# CODEC_and_Headphone_Jack.net
KiCad netlist of a schematic drawn in Altium Designer
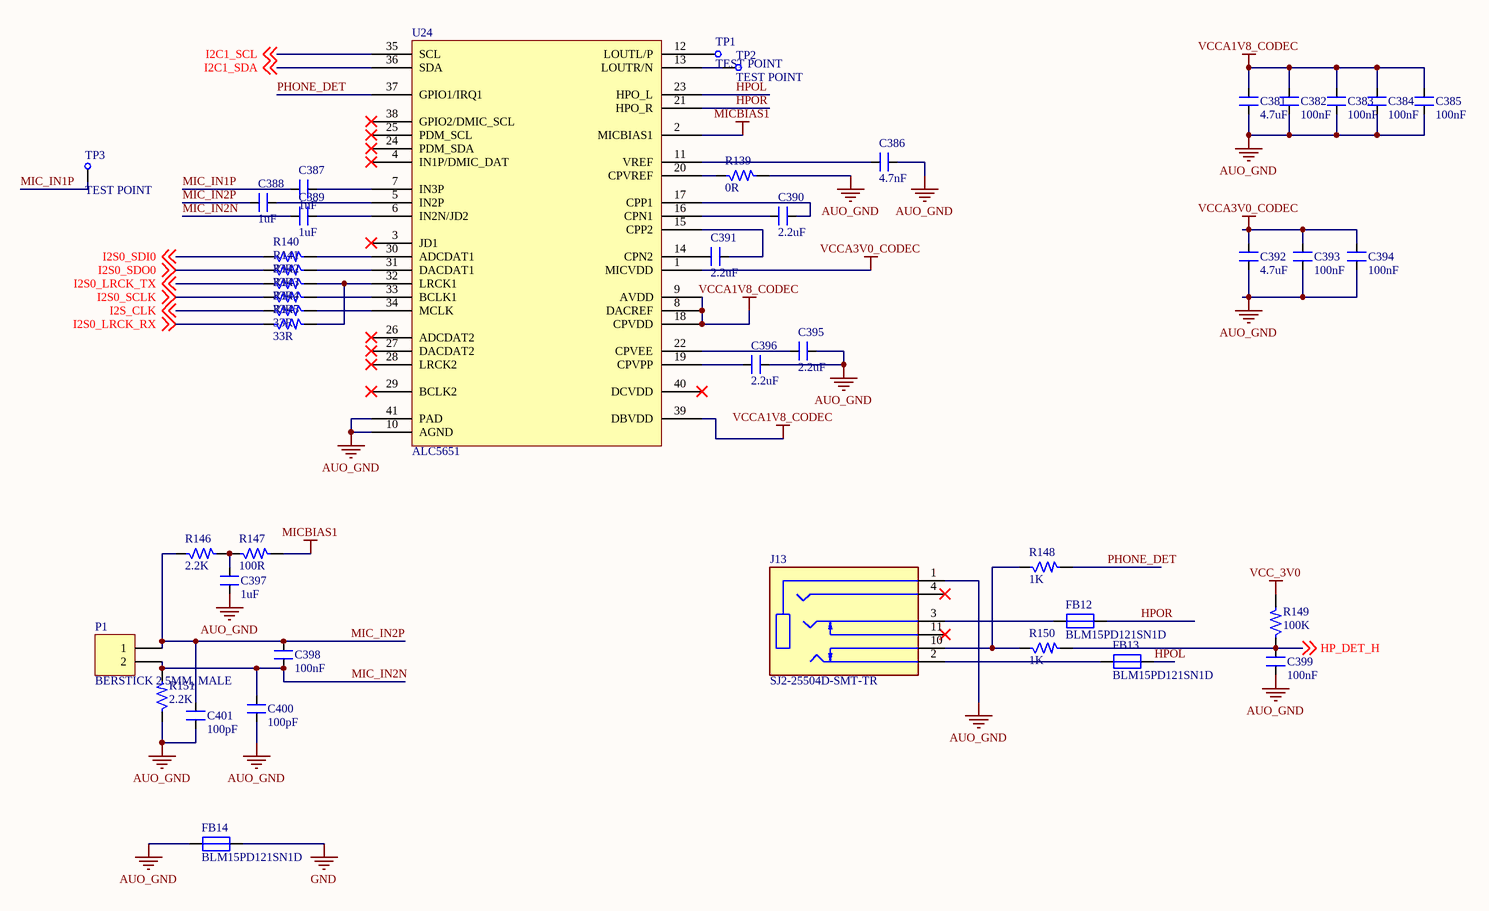
[diagram p0: CODEC and Headphone Jack.SchDoc]

(export (version "E")
  (design (tool "Eeschema 10.0.6"))
  (components
    (comp (ref "C381")
      (value "4.7uF")
      (footprint "CAP_0603")
      (description "4.7µF ±10% 16V Ceramic Capacitor X5R 0603 (1608 Metric)")
      (fields
        (field (name "MANUFACTURER") "Murata Electronics")
        (field (name "MANUFACTURER PART NUMBER") "GRM188R61C475KAAJD")
      )
      (libsource (lib "RK3399 _Module_Schlib") (part "CAP_4.7uF-16V-10%-0603"))
    )
    (comp (ref "C382")
      (value "100nF")
      (footprint "CAP_0603")
      (description "0.1µF ±10% 10V Ceramic Capacitor X7R 0603 (1608 Metric)")
      (fields
        (field (name "MANUFACTURER") "Yageo")
        (field (name "MANUFACTURER PART NUMBER") "CC0603KRX7R6BB104")
      )
      (libsource (lib "RK3399 _Module_Schlib") (part "CAP_100nF-10V-5%-0603"))
    )
    (comp (ref "C383")
      (value "100nF")
      (footprint "CAP_0603")
      (description "0.1µF ±10% 10V Ceramic Capacitor X7R 0603 (1608 Metric)")
      (fields
        (field (name "MANUFACTURER") "Yageo")
        (field (name "MANUFACTURER PART NUMBER") "CC0603KRX7R6BB104")
      )
      (libsource (lib "RK3399 _Module_Schlib") (part "CAP_100nF-10V-5%-0603"))
    )
    (comp (ref "C384")
      (value "100nF")
      (footprint "CAP_0603")
      (description "0.1µF ±10% 10V Ceramic Capacitor X7R 0603 (1608 Metric)")
      (fields
        (field (name "MANUFACTURER") "Yageo")
        (field (name "MANUFACTURER PART NUMBER") "CC0603KRX7R6BB104")
      )
      (libsource (lib "RK3399 _Module_Schlib") (part "CAP_100nF-10V-5%-0603"))
    )
    (comp (ref "C385")
      (value "100nF")
      (footprint "CAP_0603")
      (description "0.1µF ±10% 10V Ceramic Capacitor X7R 0603 (1608 Metric)")
      (fields
        (field (name "MANUFACTURER") "Yageo")
        (field (name "MANUFACTURER PART NUMBER") "CC0603KRX7R6BB104")
      )
      (libsource (lib "RK3399 _Module_Schlib") (part "CAP_100nF-10V-5%-0603"))
    )
    (comp (ref "C386")
      (value "4.7nF")
      (footprint "CAP_0603")
      (description "4700pF ±10% 10V Ceramic Capacitor X7R 0603 (1608 Metric)")
      (fields
        (field (name "MANUFACTURER") "KEMET")
        (field (name "MANUFACTURER PART NUMBER") "C0603C472K8RACTU")
      )
      (libsource (lib "RK3399 _Module_Schlib") (part "CAP_4.7nF-10V-10%-0603"))
    )
    (comp (ref "C387")
      (value "1uF")
      (footprint "CAP_0402")
      (description "1µF ±10% 10V Ceramic Capacitor X6S 0402 (1005 Metric)")
      (fields
        (field (name "MANUFACTURER") "Murata Electronics")
        (field (name "MANUFACTURER PART NUMBER") "GRT155C81A105KE01D")
      )
      (libsource (lib "RK3399 _Module_Schlib") (part "CAP_1uF-10V-10%-0402"))
    )
    (comp (ref "C388")
      (value "1uF")
      (footprint "CAP_0402")
      (description "1µF ±10% 10V Ceramic Capacitor X6S 0402 (1005 Metric)")
      (fields
        (field (name "MANUFACTURER") "Murata Electronics")
        (field (name "MANUFACTURER PART NUMBER") "GRT155C81A105KE01D")
      )
      (libsource (lib "RK3399 _Module_Schlib") (part "CAP_1uF-10V-10%-0402"))
    )
    (comp (ref "C389")
      (value "1uF")
      (footprint "CAP_0402")
      (description "1µF ±10% 10V Ceramic Capacitor X6S 0402 (1005 Metric)")
      (fields
        (field (name "MANUFACTURER") "Murata Electronics")
        (field (name "MANUFACTURER PART NUMBER") "GRT155C81A105KE01D")
      )
      (libsource (lib "RK3399 _Module_Schlib") (part "CAP_1uF-10V-10%-0402"))
    )
    (comp (ref "C390")
      (value "2.2uF")
      (footprint "CAP_0402")
      (description "2.2µF ±10% 10V Ceramic Capacitor X5R 0402 (1005 Metric)")
      (fields
        (field (name "MANUFACTURER") "Murata Electronics")
        (field (name "MANUFACTURER PART NUMBER") "GRM155R61A225KE95D")
      )
      (libsource (lib "RK3399 _Module_Schlib") (part "CAP_2.2uF-10V-10%-0402"))
    )
    (comp (ref "C391")
      (value "2.2uF")
      (footprint "CAP_0402")
      (description "2.2µF ±10% 10V Ceramic Capacitor X5R 0402 (1005 Metric)")
      (fields
        (field (name "MANUFACTURER") "Murata Electronics")
        (field (name "MANUFACTURER PART NUMBER") "GRM155R61A225KE95D")
      )
      (libsource (lib "RK3399 _Module_Schlib") (part "CAP_2.2uF-10V-10%-0402"))
    )
    (comp (ref "C392")
      (value "4.7uF")
      (footprint "CAP_0603")
      (description "4.7µF ±10% 16V Ceramic Capacitor X5R 0603 (1608 Metric)")
      (fields
        (field (name "MANUFACTURER") "Murata Electronics")
        (field (name "MANUFACTURER PART NUMBER") "GRM188R61C475KAAJD")
      )
      (libsource (lib "RK3399 _Module_Schlib") (part "CAP_4.7uF-16V-10%-0603"))
    )
    (comp (ref "C393")
      (value "100nF")
      (footprint "CAP_0603")
      (description "0.1µF ±10% 10V Ceramic Capacitor X7R 0603 (1608 Metric)")
      (fields
        (field (name "MANUFACTURER") "Yageo")
        (field (name "MANUFACTURER PART NUMBER") "CC0603KRX7R6BB104")
      )
      (libsource (lib "RK3399 _Module_Schlib") (part "CAP_100nF-10V-5%-0603"))
    )
    (comp (ref "C394")
      (value "100nF")
      (footprint "CAP_0603")
      (description "0.1µF ±10% 10V Ceramic Capacitor X7R 0603 (1608 Metric)")
      (fields
        (field (name "MANUFACTURER") "Yageo")
        (field (name "MANUFACTURER PART NUMBER") "CC0603KRX7R6BB104")
      )
      (libsource (lib "RK3399 _Module_Schlib") (part "CAP_100nF-10V-5%-0603"))
    )
    (comp (ref "C395")
      (value "2.2uF")
      (footprint "CAP_0402")
      (description "2.2µF ±10% 10V Ceramic Capacitor X5R 0402 (1005 Metric)")
      (fields
        (field (name "MANUFACTURER") "Murata Electronics")
        (field (name "MANUFACTURER PART NUMBER") "GRM155R61A225KE95D")
      )
      (libsource (lib "RK3399 _Module_Schlib") (part "CAP_2.2uF-10V-10%-0402"))
    )
    (comp (ref "C396")
      (value "2.2uF")
      (footprint "CAP_0402")
      (description "2.2µF ±10% 10V Ceramic Capacitor X5R 0402 (1005 Metric)")
      (fields
        (field (name "MANUFACTURER") "Murata Electronics")
        (field (name "MANUFACTURER PART NUMBER") "GRM155R61A225KE95D")
      )
      (libsource (lib "RK3399 _Module_Schlib") (part "CAP_2.2uF-10V-10%-0402"))
    )
    (comp (ref "C397")
      (value "1uF")
      (footprint "CAP_0603")
      (description "1µF ±10% 10V Ceramic Capacitor X5R 0603 (1608 Metric)")
      (fields
        (field (name "MANUFACTURER") "Samsung Electro-Mechanics")
        (field (name "MANUFACTURER PART NUMBER") "CL10A105KP8NNNC")
      )
      (libsource (lib "RK3399 _Module_Schlib") (part "CAP_1uF-10V-5%-0603"))
    )
    (comp (ref "C398")
      (value "100nF")
      (footprint "CAP_0603")
      (description "0.1µF ±10% 10V Ceramic Capacitor X7R 0603 (1608 Metric)")
      (fields
        (field (name "MANUFACTURER") "Yageo")
        (field (name "MANUFACTURER PART NUMBER") "CC0603KRX7R6BB104")
      )
      (libsource (lib "RK3399 _Module_Schlib") (part "CAP_100nF-10V-5%-0603"))
    )
    (comp (ref "C399")
      (value "100nF")
      (footprint "CAP_0603")
      (description "0.1µF ±10% 10V Ceramic Capacitor X7R 0603 (1608 Metric)")
      (fields
        (field (name "MANUFACTURER") "Yageo")
        (field (name "MANUFACTURER PART NUMBER") "CC0603KRX7R6BB104")
      )
      (libsource (lib "RK3399 _Module_Schlib") (part "CAP_100nF-10V-5%-0603"))
    )
    (comp (ref "C400")
      (value "100pF")
      (footprint "CAP_0603")
      (description "100pF ±10% 10V Ceramic Capacitor X7R 0603 (1608 Metric)")
      (fields
        (field (name "MANUFACTURER") "AVX Corporation")
        (field (name "MANUFACTURER PART NUMBER") "0603ZC101KAT2A")
      )
      (libsource (lib "RK3399 _Module_Schlib") (part "CAP_100pF-10V-10%-0603"))
    )
    (comp (ref "C401")
      (value "100pF")
      (footprint "CAP_0603")
      (description "100pF ±10% 10V Ceramic Capacitor X7R 0603 (1608 Metric)")
      (fields
        (field (name "MANUFACTURER") "AVX Corporation")
        (field (name "MANUFACTURER PART NUMBER") "0603ZC101KAT2A")
      )
      (libsource (lib "RK3399 _Module_Schlib") (part "CAP_100pF-10V-10%-0603"))
    )
    (comp (ref "FB12")
      (value "BLM15PD121SN1D")
      (footprint "RES_0402")
      (description "120 Ohms @ 100MHz 1 Power Line Ferrite Bead 0402 (1005 Metric) 1.3A 90mOhm")
      (fields (field (name "MANUFACTURER") "Murata Electronics"))
      (libsource (lib "RK3399 _Module_Schlib") (part "FB_120R-1.3A-100Mhz-0402"))
    )
    (comp (ref "FB13")
      (value "BLM15PD121SN1D")
      (footprint "RES_0402")
      (description "120 Ohms @ 100MHz 1 Power Line Ferrite Bead 0402 (1005 Metric) 1.3A 90mOhm")
      (fields (field (name "MANUFACTURER") "Murata Electronics"))
      (libsource (lib "RK3399 _Module_Schlib") (part "FB_120R-1.3A-100Mhz-0402"))
    )
    (comp (ref "FB14")
      (value "BLM15PD121SN1D")
      (footprint "RES_0402")
      (description "120 Ohms @ 100MHz 1 Power Line Ferrite Bead 0402 (1005 Metric) 1.3A 90mOhm")
      (fields (field (name "MANUFACTURER") "Murata Electronics"))
      (libsource (lib "RK3399 _Module_Schlib") (part "FB_120R-1.3A-100Mhz-0402"))
    )
    (comp (ref "J13")
      (value "SJ2-25504D-SMT-TR")
      (footprint "CON11_SJ2-25504D-SMT-TR_TH_RA")
      (fields (field (name "MANUFACTURER") "CUI Devices"))
      (libsource (lib "RK3399 _Module_Schlib") (part "CON-PLG_SJ2-25504D-SMT-TR-RA-TH"))
    )
    (comp (ref "P1")
      (value "BERSTICK 2.5MM, MALE")
      (footprint "CON2_100_43D62_TH_ST")
      (description "2 Pins, 1 Row 2.54mm Pitch, Straight bergstrip, Male")
      (fields (field (name "MANUFACTURER PART NUMBER") "NA") (field (name "MANUFACTURER") "Samtec"))
      (libsource (lib "RK3399 _Module_Schlib") (part "CON-BS-PLG_2X1-100-ST-TH"))
    )
    (comp (ref "R139")
      (value "0R")
      (footprint "RES_0603")
      (description "0 Ohms Jumper 0.1W, 1/10W Chip Resistor 0603 (1608 Metric) Thick Film")
      (fields
        (field (name "MANUFACTURER") "Yageo")
        (field (name "MANUFACTURER PART NUMBER") "RC0603JR-070RL")
      )
      (libsource (lib "RK3399 _Module_Schlib") (part "RES_0R-0.1W-1%-0603"))
    )
    (comp (ref "R140")
      (value "33R")
      (footprint "RES_0402")
      (description "33 Ohms ±1% 0.1W, 1/10W Chip Resistor 0402 (1005 Metric) Automotive AEC-Q200 Thick Film")
      (fields
        (field (name "MANUFACTURER") "Panasonic Electronic Components")
        (field (name "MANUFACTURER PART NUMBER") "ERJ-2RKF33R0X")
      )
      (libsource (lib "RK3399 _Module_Schlib") (part "RES_33R-0.1W-1%-0402"))
    )
    (comp (ref "R141")
      (value "33R")
      (footprint "RES_0402")
      (description "33 Ohms ±1% 0.1W, 1/10W Chip Resistor 0402 (1005 Metric) Automotive AEC-Q200 Thick Film")
      (fields
        (field (name "MANUFACTURER") "Panasonic Electronic Components")
        (field (name "MANUFACTURER PART NUMBER") "ERJ-2RKF33R0X")
      )
      (libsource (lib "RK3399 _Module_Schlib") (part "RES_33R-0.1W-1%-0402"))
    )
    (comp (ref "R142")
      (value "33R")
      (footprint "RES_0402")
      (description "33 Ohms ±1% 0.1W, 1/10W Chip Resistor 0402 (1005 Metric) Automotive AEC-Q200 Thick Film")
      (fields
        (field (name "MANUFACTURER") "Panasonic Electronic Components")
        (field (name "MANUFACTURER PART NUMBER") "ERJ-2RKF33R0X")
      )
      (libsource (lib "RK3399 _Module_Schlib") (part "RES_33R-0.1W-1%-0402"))
    )
    (comp (ref "R143")
      (value "33R")
      (footprint "RES_0402")
      (description "33 Ohms ±1% 0.1W, 1/10W Chip Resistor 0402 (1005 Metric) Automotive AEC-Q200 Thick Film")
      (fields
        (field (name "MANUFACTURER") "Panasonic Electronic Components")
        (field (name "MANUFACTURER PART NUMBER") "ERJ-2RKF33R0X")
      )
      (libsource (lib "RK3399 _Module_Schlib") (part "RES_33R-0.1W-1%-0402"))
    )
    (comp (ref "R144")
      (value "33R")
      (footprint "RES_0402")
      (description "33 Ohms ±1% 0.1W, 1/10W Chip Resistor 0402 (1005 Metric) Automotive AEC-Q200 Thick Film")
      (fields
        (field (name "MANUFACTURER") "Panasonic Electronic Components")
        (field (name "MANUFACTURER PART NUMBER") "ERJ-2RKF33R0X")
      )
      (libsource (lib "RK3399 _Module_Schlib") (part "RES_33R-0.1W-1%-0402"))
    )
    (comp (ref "R145")
      (value "33R")
      (footprint "RES_0402")
      (description "33 Ohms ±1% 0.1W, 1/10W Chip Resistor 0402 (1005 Metric) Automotive AEC-Q200 Thick Film")
      (fields
        (field (name "MANUFACTURER") "Panasonic Electronic Components")
        (field (name "MANUFACTURER PART NUMBER") "ERJ-2RKF33R0X")
      )
      (libsource (lib "RK3399 _Module_Schlib") (part "RES_33R-0.1W-1%-0402"))
    )
    (comp (ref "R146")
      (value "2.2K")
      (footprint "RES_0603")
      (description "2.2 kOhms ±1% 0.1W, 1/10W Chip Resistor 0603 (1608 Metric) Thick Film")
      (fields
        (field (name "MANUFACTURER") "Yageo")
        (field (name "MANUFACTURER PART NUMBER") "RC0603FR-072K2L")
      )
      (libsource (lib "RK3399 _Module_Schlib") (part "RES_2.2K-0.1W-1%-0603"))
    )
    (comp (ref "R147")
      (value "100R")
      (footprint "RES_0603")
      (description "100 Ohms ±1% 0.1W, 1/10W Chip Resistor 0603 (1608 Metric) Thick Film")
      (fields
        (field (name "MANUFACTURER") "Yageo")
        (field (name "MANUFACTURER PART NUMBER") "RC0603FR-07100RL")
      )
      (libsource (lib "RK3399 _Module_Schlib") (part "RES_100R-0.1W-1%-0603"))
    )
    (comp (ref "R148")
      (value "1K")
      (footprint "RES_0603")
      (description "1 kOhms ±1% 0.1W, 1/10W Chip Resistor 0603 (1608 Metric) Thick Film")
      (fields
        (field (name "MANUFACTURER") "Yageo")
        (field (name "MANUFACTURER PART NUMBER") "RC0603FR-071KL")
      )
      (libsource (lib "RK3399 _Module_Schlib") (part "RES_1K-0.1W-1%-0603"))
    )
    (comp (ref "R149")
      (value "100K")
      (footprint "RES_0603")
      (description "100 kOhms ±1% 0.1W, 1/10W Chip Resistor 0603 (1608 Metric) Automotive AEC-Q200 Thick Film")
      (fields
        (field (name "MANUFACTURER") "tackpole Electronics Inc")
        (field (name "MANUFACTURER PART NUMBER") "RMCF0603FT100K")
      )
      (libsource (lib "RK3399 _Module_Schlib") (part "RES_100K-0.1W-1%-0603"))
    )
    (comp (ref "R150")
      (value "1K")
      (footprint "RES_0603")
      (description "1 kOhms ±1% 0.1W, 1/10W Chip Resistor 0603 (1608 Metric) Thick Film")
      (fields
        (field (name "MANUFACTURER") "Yageo")
        (field (name "MANUFACTURER PART NUMBER") "RC0603FR-071KL")
      )
      (libsource (lib "RK3399 _Module_Schlib") (part "RES_1K-0.1W-1%-0603"))
    )
    (comp (ref "R151")
      (value "2.2K")
      (footprint "RES_0603")
      (description "2.2 kOhms ±1% 0.1W, 1/10W Chip Resistor 0603 (1608 Metric) Thick Film")
      (fields
        (field (name "MANUFACTURER") "Yageo")
        (field (name "MANUFACTURER PART NUMBER") "RC0603FR-072K2L")
      )
      (libsource (lib "RK3399 _Module_Schlib") (part "RES_2.2K-0.1W-1%-0603"))
    )
    (comp (ref "TP1")
      (value "TEST POINT")
      (footprint "TEST POINT_30")
      (description "0.4mm hole size Test point")
      (fields (field (name "MANUFACTURER PART NUMBER") "NA"))
      (libsource (lib "RK3399 _Module_Schlib") (part "TEST POINT"))
    )
    (comp (ref "TP2")
      (value "TEST POINT")
      (footprint "TEST POINT_30")
      (description "0.4mm hole size Test point")
      (fields (field (name "MANUFACTURER PART NUMBER") "NA"))
      (libsource (lib "RK3399 _Module_Schlib") (part "TEST POINT"))
    )
    (comp (ref "TP3")
      (value "TEST POINT")
      (footprint "TEST POINT_30")
      (description "0.4mm hole size Test point")
      (fields (field (name "MANUFACTURER PART NUMBER") "NA"))
      (libsource (lib "RK3399 _Module_Schlib") (part "TEST POINT"))
    )
    (comp (ref "U24")
      (value "ALC5651")
      (footprint "QFN40_15.7_227X227_SMD")
      (fields (field (name "MANUFACTURER") "Realtek"))
      (libsource (lib "RK3399 _Module_Schlib") (part "IC_ALC5651"))
    )
  )
  (nets
    (net (code "1") (name "/HPOL") (class "Default")
      (node (ref "FB13") (pin "2") (pinfunction "2_2") (pintype "passive"))
      (node (ref "U24") (pin "23") (pinfunction "HPO_L_23") (pintype "passive"))
    )
    (net (code "2") (name "/HPOR") (class "Default")
      (node (ref "FB12") (pin "2") (pinfunction "2_2") (pintype "passive"))
      (node (ref "U24") (pin "21") (pinfunction "HPO_R_21") (pintype "passive"))
    )
    (net (code "3") (name "/MIC_IN1P") (class "Default")
      (node (ref "C387") (pin "1") (pinfunction "1_1") (pintype "passive"))
      (node (ref "TP3") (pin "1") (pinfunction "1_1") (pintype "passive"))
    )
    (net (code "4") (name "/MIC_IN2N") (class "Default")
      (node (ref "C389") (pin "1") (pinfunction "1_1") (pintype "passive"))
      (node (ref "C398") (pin "1") (pinfunction "1_1") (pintype "passive"))
      (node (ref "C400") (pin "2") (pinfunction "2_2") (pintype "passive"))
      (node (ref "P1") (pin "2") (pinfunction "2_2") (pintype "passive"))
      (node (ref "R151") (pin "2") (pinfunction "2_2") (pintype "passive"))
    )
    (net (code "5") (name "/MIC_IN2P") (class "Default")
      (node (ref "C388") (pin "1") (pinfunction "1_1") (pintype "passive"))
      (node (ref "C398") (pin "2") (pinfunction "2_2") (pintype "passive"))
      (node (ref "C401") (pin "2") (pinfunction "2_2") (pintype "passive"))
      (node (ref "P1") (pin "1") (pinfunction "1_1") (pintype "passive"))
      (node (ref "R146") (pin "1") (pinfunction "1_1") (pintype "passive"))
    )
    (net (code "6") (name "/PHONE_DET") (class "Default")
      (node (ref "R148") (pin "2") (pinfunction "2_2") (pintype "passive"))
      (node (ref "U24") (pin "37") (pinfunction "GPIO1/IRQ1_37") (pintype "passive"))
    )
    (net (code "7") (name "AUO_GND") (class "Default")
      (node (ref "C381") (pin "1") (pinfunction "1_1") (pintype "passive"))
      (node (ref "C382") (pin "1") (pinfunction "1_1") (pintype "passive"))
      (node (ref "C383") (pin "1") (pinfunction "1_1") (pintype "passive"))
      (node (ref "C384") (pin "1") (pinfunction "1_1") (pintype "passive"))
      (node (ref "C385") (pin "1") (pinfunction "1_1") (pintype "passive"))
      (node (ref "C386") (pin "2") (pinfunction "2_2") (pintype "passive"))
      (node (ref "C392") (pin "1") (pinfunction "1_1") (pintype "passive"))
      (node (ref "C393") (pin "1") (pinfunction "1_1") (pintype "passive"))
      (node (ref "C394") (pin "1") (pinfunction "1_1") (pintype "passive"))
      (node (ref "C395") (pin "2") (pinfunction "2_2") (pintype "passive"))
      (node (ref "C396") (pin "2") (pinfunction "2_2") (pintype "passive"))
      (node (ref "C397") (pin "1") (pinfunction "1_1") (pintype "passive"))
      (node (ref "C399") (pin "1") (pinfunction "1_1") (pintype "passive"))
      (node (ref "C400") (pin "1") (pinfunction "1_1") (pintype "passive"))
      (node (ref "C401") (pin "1") (pinfunction "1_1") (pintype "passive"))
      (node (ref "FB14") (pin "1") (pinfunction "1_1") (pintype "passive"))
      (node (ref "J13") (pin "1") (pinfunction "SLEEVE_1") (pintype "passive"))
      (node (ref "R139") (pin "2") (pinfunction "2_2") (pintype "passive"))
      (node (ref "R151") (pin "1") (pinfunction "1_1") (pintype "passive"))
      (node (ref "U24") (pin "10") (pinfunction "AGND_10") (pintype "passive"))
      (node (ref "U24") (pin "41") (pinfunction "PAD_41") (pintype "passive"))
    )
    (net (code "8") (name "GND") (class "Default")
      (node (ref "FB14") (pin "2") (pinfunction "2_2") (pintype "passive"))
    )
    (net (code "9") (name "HP_DET_H") (class "Default")
      (node (ref "C399") (pin "2") (pinfunction "2_2") (pintype "passive"))
      (node (ref "R149") (pin "1") (pinfunction "1_1") (pintype "passive"))
      (node (ref "R150") (pin "2") (pinfunction "2_2") (pintype "passive"))
    )
    (net (code "10") (name "I2C1_SCL") (class "Default")
      (node (ref "U24") (pin "35") (pinfunction "SCL_35") (pintype "passive"))
    )
    (net (code "11") (name "I2C1_SDA") (class "Default")
      (node (ref "U24") (pin "36") (pinfunction "SDA_36") (pintype "passive"))
    )
    (net (code "12") (name "I2S0_LRCK_RX") (class "Default")
      (node (ref "R145") (pin "1") (pinfunction "1_1") (pintype "passive"))
    )
    (net (code "13") (name "I2S0_LRCK_TX") (class "Default")
      (node (ref "R142") (pin "1") (pinfunction "1_1") (pintype "passive"))
    )
    (net (code "14") (name "I2S0_SCLK") (class "Default")
      (node (ref "R143") (pin "1") (pinfunction "1_1") (pintype "passive"))
    )
    (net (code "15") (name "I2S0_SDI0") (class "Default")
      (node (ref "R140") (pin "1") (pinfunction "1_1") (pintype "passive"))
    )
    (net (code "16") (name "I2S0_SDO0") (class "Default")
      (node (ref "R141") (pin "1") (pinfunction "1_1") (pintype "passive"))
    )
    (net (code "17") (name "I2S_CLK") (class "Default")
      (node (ref "R144") (pin "1") (pinfunction "1_1") (pintype "passive"))
    )
    (net (code "18") (name "MICBIAS1") (class "Default")
      (node (ref "R147") (pin "2") (pinfunction "2_2") (pintype "passive"))
      (node (ref "U24") (pin "2") (pinfunction "MICBIAS1_2") (pintype "passive"))
    )
    (net (code "19") (name "Net-(C397-Pad2)") (class "Default")
      (node (ref "C397") (pin "2") (pinfunction "2_2") (pintype "passive"))
      (node (ref "R146") (pin "2") (pinfunction "2_2") (pintype "passive"))
      (node (ref "R147") (pin "1") (pinfunction "1_1") (pintype "passive"))
    )
    (net (code "20") (name "Net-(J13-RING1)") (class "Default")
      (node (ref "FB12") (pin "1") (pinfunction "1_1") (pintype "passive"))
      (node (ref "J13") (pin "3") (pinfunction "RING1_3") (pintype "passive"))
    )
    (net (code "21") (name "Net-(J13-TIP)") (class "Default")
      (node (ref "FB13") (pin "1") (pinfunction "1_1") (pintype "passive"))
      (node (ref "J13") (pin "2") (pinfunction "TIP_2") (pintype "passive"))
    )
    (net (code "22") (name "Net-(J13-TIP_SWITCH)") (class "Default")
      (node (ref "J13") (pin "10") (pinfunction "TIP_SWITCH_10") (pintype "passive"))
      (node (ref "R148") (pin "1") (pinfunction "1_1") (pintype "passive"))
      (node (ref "R150") (pin "1") (pinfunction "1_1") (pintype "passive"))
    )
    (net (code "23") (name "Net-(U24-ADCDAT1)") (class "Default")
      (node (ref "R140") (pin "2") (pinfunction "2_2") (pintype "passive"))
      (node (ref "U24") (pin "30") (pinfunction "ADCDAT1_30") (pintype "passive"))
    )
    (net (code "24") (name "Net-(U24-BCLK1)") (class "Default")
      (node (ref "R143") (pin "2") (pinfunction "2_2") (pintype "passive"))
      (node (ref "U24") (pin "33") (pinfunction "BCLK1_33") (pintype "passive"))
    )
    (net (code "25") (name "Net-(U24-CPN1)") (class "Default")
      (node (ref "C390") (pin "1") (pinfunction "1_1") (pintype "passive"))
      (node (ref "U24") (pin "16") (pinfunction "CPN1_16") (pintype "passive"))
    )
    (net (code "26") (name "Net-(U24-CPN2)") (class "Default")
      (node (ref "C391") (pin "1") (pinfunction "1_1") (pintype "passive"))
      (node (ref "U24") (pin "14") (pinfunction "CPN2_14") (pintype "passive"))
    )
    (net (code "27") (name "Net-(U24-CPP1)") (class "Default")
      (node (ref "C390") (pin "2") (pinfunction "2_2") (pintype "passive"))
      (node (ref "U24") (pin "17") (pinfunction "CPP1_17") (pintype "passive"))
    )
    (net (code "28") (name "Net-(U24-CPP2)") (class "Default")
      (node (ref "C391") (pin "2") (pinfunction "2_2") (pintype "passive"))
      (node (ref "U24") (pin "15") (pinfunction "CPP2_15") (pintype "passive"))
    )
    (net (code "29") (name "Net-(U24-CPVEE)") (class "Default")
      (node (ref "C395") (pin "1") (pinfunction "1_1") (pintype "passive"))
      (node (ref "U24") (pin "22") (pinfunction "CPVEE_22") (pintype "passive"))
    )
    (net (code "30") (name "Net-(U24-CPVPP)") (class "Default")
      (node (ref "C396") (pin "1") (pinfunction "1_1") (pintype "passive"))
      (node (ref "U24") (pin "19") (pinfunction "CPVPP_19") (pintype "passive"))
    )
    (net (code "31") (name "Net-(U24-CPVREF)") (class "Default")
      (node (ref "R139") (pin "1") (pinfunction "1_1") (pintype "passive"))
      (node (ref "U24") (pin "20") (pinfunction "CPVREF_20") (pintype "passive"))
    )
    (net (code "32") (name "Net-(U24-DACDAT1)") (class "Default")
      (node (ref "R141") (pin "2") (pinfunction "2_2") (pintype "passive"))
      (node (ref "U24") (pin "31") (pinfunction "DACDAT1_31") (pintype "passive"))
    )
    (net (code "33") (name "Net-(U24-IN2N{slash}JD2)") (class "Default")
      (node (ref "C389") (pin "2") (pinfunction "2_2") (pintype "passive"))
      (node (ref "U24") (pin "6") (pinfunction "IN2N/JD2_6") (pintype "passive"))
    )
    (net (code "34") (name "Net-(U24-IN2P)") (class "Default")
      (node (ref "C388") (pin "2") (pinfunction "2_2") (pintype "passive"))
      (node (ref "U24") (pin "5") (pinfunction "IN2P_5") (pintype "passive"))
    )
    (net (code "35") (name "Net-(U24-IN3P)") (class "Default")
      (node (ref "C387") (pin "2") (pinfunction "2_2") (pintype "passive"))
      (node (ref "U24") (pin "7") (pinfunction "IN3P_7") (pintype "passive"))
    )
    (net (code "36") (name "Net-(U24-LOUTL{slash}P)") (class "Default")
      (node (ref "TP1") (pin "1") (pinfunction "1_1") (pintype "passive"))
      (node (ref "U24") (pin "12") (pinfunction "LOUTL/P_12") (pintype "passive"))
    )
    (net (code "37") (name "Net-(U24-LOUTR{slash}N)") (class "Default")
      (node (ref "TP2") (pin "1") (pinfunction "1_1") (pintype "passive"))
      (node (ref "U24") (pin "13") (pinfunction "LOUTR/N_13") (pintype "passive"))
    )
    (net (code "38") (name "Net-(U24-LRCK1)") (class "Default")
      (node (ref "R142") (pin "2") (pinfunction "2_2") (pintype "passive"))
      (node (ref "R145") (pin "2") (pinfunction "2_2") (pintype "passive"))
      (node (ref "U24") (pin "32") (pinfunction "LRCK1_32") (pintype "passive"))
    )
    (net (code "39") (name "Net-(U24-MCLK)") (class "Default")
      (node (ref "R144") (pin "2") (pinfunction "2_2") (pintype "passive"))
      (node (ref "U24") (pin "34") (pinfunction "MCLK_34") (pintype "passive"))
    )
    (net (code "40") (name "Net-(U24-VREF)") (class "Default")
      (node (ref "C386") (pin "1") (pinfunction "1_1") (pintype "passive"))
      (node (ref "U24") (pin "11") (pinfunction "VREF_11") (pintype "passive"))
    )
    (net (code "41") (name "VCCA1V8_CODEC") (class "Default")
      (node (ref "C381") (pin "2") (pinfunction "2_2") (pintype "passive"))
      (node (ref "C382") (pin "2") (pinfunction "2_2") (pintype "passive"))
      (node (ref "C383") (pin "2") (pinfunction "2_2") (pintype "passive"))
      (node (ref "C384") (pin "2") (pinfunction "2_2") (pintype "passive"))
      (node (ref "C385") (pin "2") (pinfunction "2_2") (pintype "passive"))
      (node (ref "U24") (pin "18") (pinfunction "CPVDD_18") (pintype "passive"))
      (node (ref "U24") (pin "39") (pinfunction "DBVDD_39") (pintype "passive"))
      (node (ref "U24") (pin "8") (pinfunction "DACREF_8") (pintype "passive"))
      (node (ref "U24") (pin "9") (pinfunction "AVDD_9") (pintype "passive"))
    )
    (net (code "42") (name "VCCA3V0_CODEC") (class "Default")
      (node (ref "C392") (pin "2") (pinfunction "2_2") (pintype "passive"))
      (node (ref "C393") (pin "2") (pinfunction "2_2") (pintype "passive"))
      (node (ref "C394") (pin "2") (pinfunction "2_2") (pintype "passive"))
      (node (ref "U24") (pin "1") (pinfunction "MICVDD_1") (pintype "passive"))
    )
    (net (code "43") (name "VCC_3V0") (class "Default")
      (node (ref "R149") (pin "2") (pinfunction "2_2") (pintype "passive"))
    )
    (net (code "44") (name "unconnected-(J13-RING1_SWITCH-Pad11)") (class "Default")
      (node (ref "J13") (pin "11") (pinfunction "RING1_SWITCH_11") (pintype "passive+no_connect"))
    )
    (net (code "45") (name "unconnected-(J13-RING2-Pad4)") (class "Default")
      (node (ref "J13") (pin "4") (pinfunction "RING2_4") (pintype "passive+no_connect"))
    )
    (net (code "46") (name "unconnected-(U24-ADCDAT2-Pad26)") (class "Default")
      (node (ref "U24") (pin "26") (pinfunction "ADCDAT2_26") (pintype "passive+no_connect"))
    )
    (net (code "47") (name "unconnected-(U24-BCLK2-Pad29)") (class "Default")
      (node (ref "U24") (pin "29") (pinfunction "BCLK2_29") (pintype "passive+no_connect"))
    )
    (net (code "48") (name "unconnected-(U24-DACDAT2-Pad27)") (class "Default")
      (node (ref "U24") (pin "27") (pinfunction "DACDAT2_27") (pintype "passive+no_connect"))
    )
    (net (code "49") (name "unconnected-(U24-DCVDD-Pad40)") (class "Default")
      (node (ref "U24") (pin "40") (pinfunction "DCVDD_40") (pintype "passive+no_connect"))
    )
    (net (code "50") (name "unconnected-(U24-GPIO2{slash}DMIC_SCL-Pad38)") (class "Default")
      (node (ref "U24") (pin "38") (pinfunction "GPIO2/DMIC_SCL_38") (pintype "passive+no_connect"))
    )
    (net (code "51") (name "unconnected-(U24-IN1P{slash}DMIC_DAT-Pad4)") (class "Default")
      (node (ref "U24") (pin "4") (pinfunction "IN1P/DMIC_DAT_4") (pintype "passive+no_connect"))
    )
    (net (code "52") (name "unconnected-(U24-JD1-Pad3)") (class "Default")
      (node (ref "U24") (pin "3") (pinfunction "JD1_3") (pintype "passive+no_connect"))
    )
    (net (code "53") (name "unconnected-(U24-LRCK2-Pad28)") (class "Default")
      (node (ref "U24") (pin "28") (pinfunction "LRCK2_28") (pintype "passive+no_connect"))
    )
    (net (code "54") (name "unconnected-(U24-PDM_SCL-Pad25)") (class "Default")
      (node (ref "U24") (pin "25") (pinfunction "PDM_SCL_25") (pintype "passive+no_connect"))
    )
    (net (code "55") (name "unconnected-(U24-PDM_SDA-Pad24)") (class "Default")
      (node (ref "U24") (pin "24") (pinfunction "PDM_SDA_24") (pintype "passive+no_connect"))
    )
  )
)
